# PAGE2-MAIN.net
KiCad netlist of a schematic drawn in Altium Designer
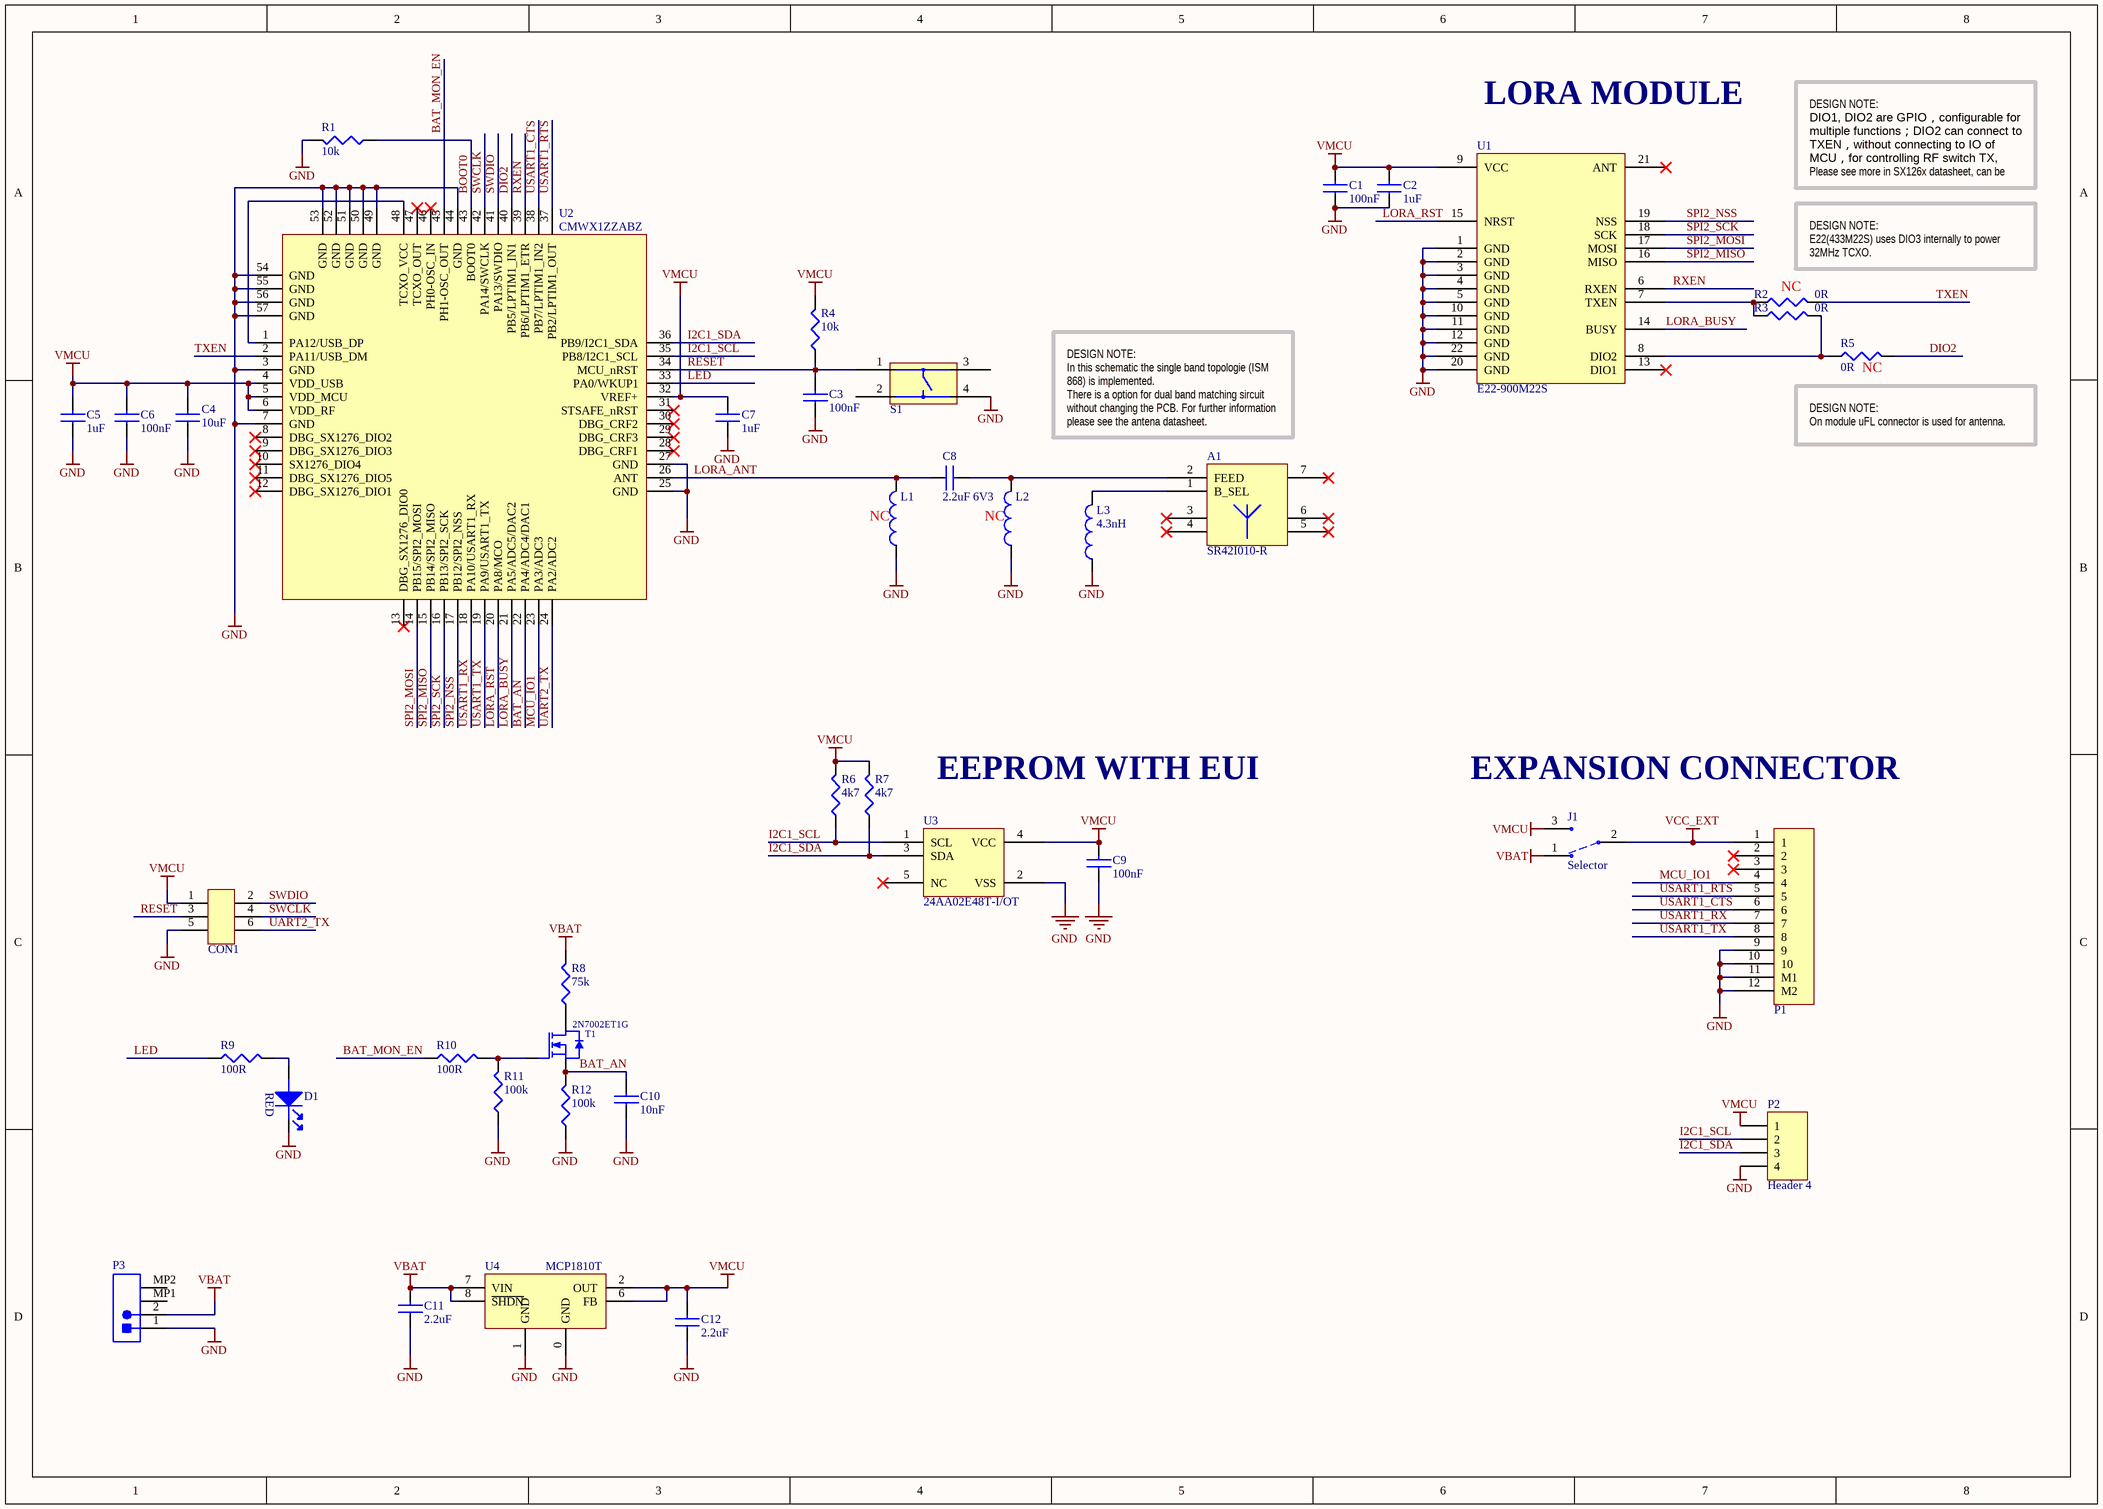
[diagram p0: PAGE2-MAIN.SchDoc]

(export (version "E")
  (design (tool "Eeschema 10.0.6"))
  (components
    (comp (ref "A1")
      (value "SR42I010-R")
      (footprint "LORA_PCB_ANTENNA")
      (description "Antenna SMD -4dBi Gain 870MHz/928MHz Automotive 7-Pin SMD T/R")
      (fields (field (name "MANUFACTURER") "Antenova"))
      (libsource (lib "Arribada-turtle-gps-tag-lora-addon") (part "SR42I010-R"))
    )
    (comp (ref "C1")
      (value "100nF")
      (footprint "CAP0603")
      (description "MURATA - GRM188R71C104KA01J - CAP, MLCC, X7R, 0.1UF, 16V, 0603")
      (fields
        (field (name "MANUFACTURER") "MURATA")
        (field (name "MANUFACTURER PART NUMBER") "GRM188R71C104KA01J")
      )
      (libsource (lib "Passive") (part "C - 100nF"))
    )
    (comp (ref "C2")
      (value "1uF")
      (footprint "CAP0603")
      (description "MURATA - GRM188R61H105KAALD - CAP, MLCC, X5R, 1UF, 50V, 0603")
      (fields
        (field (name "MANUFACTURER") "MURATA")
        (field (name "MANUFACTURER PART NUMBER") "GRM188R61H105KAALD")
      )
      (libsource (lib "Passive") (part "C - 1uF"))
    )
    (comp (ref "C3")
      (value "100nF")
      (footprint "CAP0603")
      (description "MURATA - GRM188R71C104KA01J - CAP, MLCC, X7R, 0.1UF, 16V, 0603")
      (fields
        (field (name "MANUFACTURER") "MURATA")
        (field (name "MANUFACTURER PART NUMBER") "GRM188R71C104KA01J")
      )
      (libsource (lib "Passive") (part "C - 100nF"))
    )
    (comp (ref "C4")
      (value "10uF")
      (footprint "CAP0603")
      (description "10uf/0603/20%")
      (fields
        (field (name "MANUFACTURER") "KEMET")
        (field (name "MANUFACTURER PART NUMBER") "C0603C106M8PACTU")
      )
      (libsource (lib "pira-smart-schlib") (part "10uF"))
    )
    (comp (ref "C5")
      (value "1uF")
      (footprint "CAP0603")
      (description "MURATA - GRM188R61H105KAALD - CAP, MLCC, X5R, 1UF, 50V, 0603")
      (fields
        (field (name "MANUFACTURER") "MURATA")
        (field (name "MANUFACTURER PART NUMBER") "GRM188R61H105KAALD")
      )
      (libsource (lib "Passive") (part "C - 1uF"))
    )
    (comp (ref "C6")
      (value "100nF")
      (footprint "CAP0603")
      (description "MURATA - GRM188R71C104KA01J - CAP, MLCC, X7R, 0.1UF, 16V, 0603")
      (fields
        (field (name "MANUFACTURER") "MURATA")
        (field (name "MANUFACTURER PART NUMBER") "GRM188R71C104KA01J")
      )
      (libsource (lib "Passive") (part "C - 100nF"))
    )
    (comp (ref "C7")
      (value "1uF")
      (footprint "CAP0603")
      (description "MURATA - GRM188R61H105KAALD - CAP, MLCC, X5R, 1UF, 50V, 0603")
      (fields
        (field (name "MANUFACTURER") "MURATA")
        (field (name "MANUFACTURER PART NUMBER") "GRM188R61H105KAALD")
      )
      (libsource (lib "Passive") (part "C - 1uF"))
    )
    (comp (ref "C8")
      (value "2.2uF 6V3")
      (footprint "CAP0402")
      (description "CAP CER 2.2UF 6.3V 20% X5R 0402")
      (fields
        (field (name "MANUFACTURER") "Murata")
        (field (name "MANUFACTURER PART NUMBER") "GRM155R60J225ME15D")
      )
      (libsource (lib "Passive") (part "C - 2.2uF/6V3/0402"))
    )
    (comp (ref "C9")
      (value "100nF")
      (footprint "CAP0603")
      (description "MURATA - GRM188R71C104KA01J - CAP, MLCC, X7R, 0.1UF, 16V, 0603")
      (fields
        (field (name "MANUFACTURER") "MURATA")
        (field (name "MANUFACTURER PART NUMBER") "GRM188R71C104KA01J")
      )
      (libsource (lib "Passive") (part "C - 100nF"))
    )
    (comp (ref "C10")
      (value "10nF")
      (footprint "CAP0603")
      (description "KEMET - C0603X103K5RECAUTO - CAP, MLCC, AEC-Q200, X7R, 0.01UF, 50V")
      (fields
        (field (name "MANUFACTURER") "TDK EPCOS")
        (field (name "MANUFACTURER PART NUMBER") "C0603X103K5RECAUTO")
      )
      (libsource (lib "Passive") (part "C - 10nF"))
    )
    (comp (ref "C11")
      (value "2.2uF")
      (footprint "CAP0805")
      (description "Multilayer Ceramic Capacitors MLCC - SMD/SMT 2.2uF 25V X7R 10%")
      (fields
        (field (name "MANUFACTURER") "Yageo")
        (field (name "MANUFACTURER PART NUMBER") "CC0805KKX7R8BB225")
      )
      (libsource (lib "Passive") (part "C - 2.2uF/0805"))
    )
    (comp (ref "C12")
      (value "2.2uF")
      (footprint "CAP0805")
      (description "Multilayer Ceramic Capacitors MLCC - SMD/SMT 2.2uF 25V X7R 10%")
      (fields
        (field (name "MANUFACTURER") "Yageo")
        (field (name "MANUFACTURER PART NUMBER") "CC0805KKX7R8BB225")
      )
      (libsource (lib "Passive") (part "C - 2.2uF/0805"))
    )
    (comp (ref "CON1")
      (value "Tag connect")
      (footprint "TC2030-IDC-NL")
      (libsource (lib "Connectors") (part "tag connecot 6 pin"))
    )
    (comp (ref "D1")
      (value "LED RED")
      (footprint "LED0603")
      (description "BROADCOM LIMITED - HSMS-C190 - LED, RED, 10MCD, 626NM")
      (fields
        (field (name "MANUFACTURER") "BROADCOM LIMITED")
        (field (name "MANUFACTURER PART NUMBER") "HSMS-C190")
      )
      (libsource (lib "Active") (part "LED - LED RED"))
    )
    (comp (ref "J1")
      (value "Selector")
      (footprint "Selector")
      (libsource (lib "Connectors") (part "Selector"))
    )
    (comp (ref "L1")
      (value "4.3nH")
      (footprint "IND0402")
      (description "Inductor RF Chip Multi-Layer 4.3nH 0.3nH 100MHz 8Q-Factor Air 300mA 210mOhm DCR 0402 Paper T/R")
      (fields
        (field (name "MANUFACTURER") "Murata")
        (field (name "MANUFACTURER PART NUMBER") "LQG15HN4N3S02D")
      )
      (libsource (lib "Passive") (part "L - 4.3nH/0402"))
    )
    (comp (ref "L2")
      (value "4.3nH")
      (footprint "IND0402")
      (description "Inductor RF Chip Multi-Layer 4.3nH 0.3nH 100MHz 8Q-Factor Air 300mA 210mOhm DCR 0402 Paper T/R")
      (fields
        (field (name "MANUFACTURER") "Murata")
        (field (name "MANUFACTURER PART NUMBER") "LQG15HN4N3S02D")
      )
      (libsource (lib "Passive") (part "L - 4.3nH/0402"))
    )
    (comp (ref "L3")
      (value "4.3nH")
      (footprint "IND0402")
      (description "Inductor RF Chip Multi-Layer 4.3nH 0.3nH 100MHz 8Q-Factor Air 300mA 210mOhm DCR 0402 Paper T/R")
      (fields
        (field (name "MANUFACTURER") "Murata")
        (field (name "MANUFACTURER PART NUMBER") "LQG15HN4N3S02D")
      )
      (libsource (lib "Inductors_Schlib") (part "4.3nH/0402"))
    )
    (comp (ref "P1")
      (value "53261-1071")
      (footprint "53261-1071")
      (description "Headers & Wire Housings 1.25MM HDR 10 CKT Right-Angle")
      (fields (field (name "MANUFACTURER") "Molex"))
      (libsource (lib "Schlib") (part "53261-1071"))
    )
    (comp (ref "P2")
      (value "Header 4")
      (footprint "HDR1X4")
      (description "Header, 4-Pin")
      (fields (field (name "PUBLISHER") "Altium Limited"))
      (libsource (lib "Miscellaneous Connectors") (part "Header 4"))
    )
    (comp (ref "P3")
      (value "S2B-PH-SM4-TB(LF)(SN)")
      (footprint "JST- S2B-PH-SM4-TB(LF)(SN)-2_V")
      (description "Male Header, Pitch 2 mm, 1 x 2 Position, Height 5.5 mm, -25 to 85 degC, RoHS, Tape and Reel")
      (libsource (lib "Schlib") (part "CMP-1755-00001-1"))
    )
    (comp (ref "R1")
      (value "10k")
      (footprint "RES0603")
      (description "MULTICOMP - MCMR06X103 JTL - RES, CERAMIC, 10K, 5%, 0.1W, 0603")
      (fields
        (field (name "MANUFACTURER") "MULTICOMP")
        (field (name "MANUFACTURER PART NUMBER") "MCMR06X103 JTL")
      )
      (libsource (lib "Passive") (part "R - 10k"))
    )
    (comp (ref "R2")
      (value "0R")
      (footprint "RES0603")
      (description "BOURNS - CR0603-J/-000ELF - RES, THICK FILM, 0R, 5%, 0.1W, 0603")
      (fields
        (field (name "MANUFACTURER") "BOURNS")
        (field (name "MANUFACTURER PART NUMBER") "CR0603-J/-000ELF")
      )
      (libsource (lib "Passive") (part "R - 0R"))
    )
    (comp (ref "R3")
      (value "0R")
      (footprint "RES0603")
      (description "BOURNS - CR0603-J/-000ELF - RES, THICK FILM, 0R, 5%, 0.1W, 0603")
      (fields
        (field (name "MANUFACTURER") "BOURNS")
        (field (name "MANUFACTURER PART NUMBER") "CR0603-J/-000ELF")
      )
      (libsource (lib "Passive") (part "R - 0R"))
    )
    (comp (ref "R4")
      (value "10k")
      (footprint "RES0603")
      (description "MULTICOMP - MCMR06X103 JTL - RES, CERAMIC, 10K, 5%, 0.1W, 0603")
      (fields
        (field (name "MANUFACTURER") "MULTICOMP")
        (field (name "MANUFACTURER PART NUMBER") "MCMR06X103 JTL")
      )
      (libsource (lib "Passive") (part "R - 10k"))
    )
    (comp (ref "R5")
      (value "0R")
      (footprint "RES0603")
      (description "BOURNS - CR0603-J/-000ELF - RES, THICK FILM, 0R, 5%, 0.1W, 0603")
      (fields
        (field (name "MANUFACTURER") "BOURNS")
        (field (name "MANUFACTURER PART NUMBER") "CR0603-J/-000ELF")
      )
      (libsource (lib "Passive") (part "R - 0R"))
    )
    (comp (ref "R6")
      (value "4k7")
      (footprint "RES0603")
      (description "MULTICOMP - MCMR06X4701FTL - RES, CERAMIC, 4K7, 1%, 0.1W, 0603")
      (fields
        (field (name "MANUFACTURER") "MULTICOMP")
        (field (name "MANUFACTURER PART NUMBER") "MCMR06X4701FTL")
      )
      (libsource (lib "Passive") (part "R - 4k7"))
    )
    (comp (ref "R7")
      (value "4k7")
      (footprint "RES0603")
      (description "MULTICOMP - MCMR06X4701FTL - RES, CERAMIC, 4K7, 1%, 0.1W, 0603")
      (fields
        (field (name "MANUFACTURER") "MULTICOMP")
        (field (name "MANUFACTURER PART NUMBER") "MCMR06X4701FTL")
      )
      (libsource (lib "Passive") (part "R - 4k7"))
    )
    (comp (ref "R8")
      (value "75k")
      (footprint "RES0603")
      (description "MULTICOMP - MCSR06X7502FTL - RES, CERAMIC, 75K, 1%, 0.1W, 0603")
      (fields
        (field (name "MANUFACTURER") "MULTICOMP")
        (field (name "MANUFACTURER PART NUMBER") "MCSR06X7502FTL")
      )
      (libsource (lib "Passive") (part "R - 75k"))
    )
    (comp (ref "R9")
      (value "100R")
      (footprint "RES0603")
      (description "MULTICOMP - MC0063W06031100R - RES, THICK FILM, 100R, 1%, 0.063W, 0603")
      (fields
        (field (name "MANUFACTURER") "MULTICOMP")
        (field (name "MANUFACTURER PART NUMBER") "MC0063W06031100R")
      )
      (libsource (lib "Passive") (part "R - 100R"))
    )
    (comp (ref "R10")
      (value "100R")
      (footprint "RES0603")
      (description "MULTICOMP - MC0063W06031100R - RES, THICK FILM, 100R, 1%, 0.063W, 0603")
      (fields
        (field (name "MANUFACTURER") "MULTICOMP")
        (field (name "MANUFACTURER PART NUMBER") "MC0063W06031100R")
      )
      (libsource (lib "Passive") (part "R - 100R"))
    )
    (comp (ref "R11")
      (value "100k")
      (footprint "RES0603")
      (description "MULTICOMP - MCMR06X104 JTL - RES, CERAMIC, 100K, 5%, 0.1W, 0603")
      (fields
        (field (name "MANUFACTURER") "MULTICOMP")
        (field (name "MANUFACTURER PART NUMBER") "MCMR06X104 JTL")
      )
      (libsource (lib "Passive") (part "R - 100k"))
    )
    (comp (ref "R12")
      (value "100k")
      (footprint "RES0603")
      (description "MULTICOMP - MCMR06X104 JTL - RES, CERAMIC, 100K, 5%, 0.1W, 0603")
      (fields
        (field (name "MANUFACTURER") "MULTICOMP")
        (field (name "MANUFACTURER PART NUMBER") "MCMR06X104 JTL")
      )
      (libsource (lib "Passive") (part "R - 100k"))
    )
    (comp (ref "S1")
      (value "KMR221NGLFS")
      (footprint "SW")
      (description "SWITCH TACTILE SPST-NO 0.05A 32V")
      (fields (field (name "MANUFACTURER") "ITT C&K"))
      (libsource (lib "Schlib") (part "KMR221NGLFS"))
    )
    (comp (ref "T1")
      (value "2N7002ET1G")
      (footprint "Active:SOT23-3AL")
      (description "MOSFET Transistor, N Channel, 310 mA, 60 V, 0.86 ohm, 10 V, 1 V")
      (fields (field (name "AUTHOR") "Ciril Golob"))
      (libsource (lib "Active") (part "T_M - 2N7002ET1G"))
    )
    (comp (ref "U1")
      (value "E22-900M22S")
      (footprint "E22-900M22S")
      (libsource (lib "Lora_modules") (part "E22-900M22S"))
    )
    (comp (ref "U2")
      (value "CMWX1ZZABZ")
      (footprint "Lora Module ES0")
      (description "RF Module, FSK, OOK, LoRa, 4.8Kbps, 915MHz, -135.5dBm, 2.2V to 3.6V, I2C, SPI, UART, USB")
      (fields
        (field (name "MANUFACTURER") "Murata")
        (field (name "MANUFACTURER PART NUMBER") "CMWX1ZZABZ-091")
      )
      (libsource (lib "Active") (part "MCU - CMWX1ZZABZ"))
    )
    (comp (ref "U3")
      (value "24AA02E48T-I/OT")
      (footprint "SOT95P280X145-5N")
      (fields (field (name "MANUFACTURER") "Microchip"))
      (libsource (lib "Arribada-turtle-gps-tag-lora-addon") (part "24AA02E48T-I/OT"))
    )
    (comp (ref "U4")
      (value "MCP1810T")
      (footprint "VDFN_2x2")
      (description "LDO Voltage Regulator, Fixed, 2.5 V to 5.5 V in, 2.5 V/150 mA out, 380 mV drop")
      (fields
        (field (name "MANUFACTURER") "ON SEMICONDUCTOR")
        (field (name "MANUFACTURER PART NUMBER") "LM2596DSADJG")
      )
      (libsource (lib "Active") (part "V_LIN - MCP1810T"))
    )
  )
  (nets
    (net (code "1") (name "/BAT_AN") (class "Default")
      (node (ref "C10") (pin "2") (pinfunction "2_2") (pintype "passive"))
      (node (ref "R12") (pin "2") (pinfunction "2_2") (pintype "passive"))
      (node (ref "T1") (pin "2") (pinfunction "S_2") (pintype "passive"))
      (node (ref "U2") (pin "22") (pinfunction "PA4/ADC4/DAC1_22") (pintype "passive"))
    )
    (net (code "2") (name "/BAT_MON_EN") (class "Default")
      (node (ref "R10") (pin "1") (pinfunction "1_1") (pintype "passive"))
      (node (ref "U2") (pin "45") (pinfunction "PH1-OSC_OUT_45") (pintype "passive"))
    )
    (net (code "3") (name "/BOOT0") (class "Default")
      (node (ref "R1") (pin "1") (pinfunction "1_1") (pintype "passive"))
      (node (ref "U2") (pin "43") (pinfunction "BOOT0_43") (pintype "passive"))
    )
    (net (code "4") (name "/DIO2") (class "Default")
      (node (ref "R5") (pin "2") (pinfunction "2_2") (pintype "passive"))
      (node (ref "U2") (pin "40") (pinfunction "PB5/LPTIM1_IN1_40") (pintype "passive"))
    )
    (net (code "5") (name "/I2C1_SCL") (class "Default")
      (node (ref "P2") (pin "2") (pinfunction "2_2") (pintype "passive"))
      (node (ref "R6") (pin "1") (pinfunction "1_1") (pintype "passive"))
      (node (ref "U2") (pin "35") (pinfunction "PB8/I2C1_SCL_35") (pintype "passive"))
      (node (ref "U3") (pin "1") (pinfunction "SCL_1") (pintype "passive"))
    )
    (net (code "6") (name "/I2C1_SDA") (class "Default")
      (node (ref "P2") (pin "3") (pinfunction "3_3") (pintype "passive"))
      (node (ref "R7") (pin "1") (pinfunction "1_1") (pintype "passive"))
      (node (ref "U2") (pin "36") (pinfunction "PB9/I2C1_SDA_36") (pintype "passive"))
      (node (ref "U3") (pin "3") (pinfunction "SDA_3") (pintype "passive"))
    )
    (net (code "7") (name "/LED") (class "Default")
      (node (ref "R9") (pin "1") (pinfunction "1_1") (pintype "passive"))
      (node (ref "U2") (pin "33") (pinfunction "PA0/WKUP1_33") (pintype "passive"))
    )
    (net (code "8") (name "/LORA_ANT") (class "Default")
      (node (ref "C8") (pin "1") (pinfunction "1_1") (pintype "passive"))
      (node (ref "L1") (pin "2") (pinfunction "2_2") (pintype "passive"))
      (node (ref "U2") (pin "26") (pinfunction "ANT_26") (pintype "passive"))
    )
    (net (code "9") (name "/LORA_BUSY") (class "Default")
      (node (ref "U1") (pin "14") (pinfunction "BUSY_14") (pintype "passive"))
      (node (ref "U2") (pin "21") (pinfunction "PA5/ADC5/DAC2_21") (pintype "passive"))
    )
    (net (code "10") (name "/LORA_RST") (class "Default")
      (node (ref "U1") (pin "15") (pinfunction "NRST_15") (pintype "passive"))
      (node (ref "U2") (pin "20") (pinfunction "PA8/MCO_20") (pintype "passive"))
    )
    (net (code "11") (name "/MCU_IO1") (class "Default")
      (node (ref "P1") (pin "4") (pinfunction "4_4") (pintype "passive"))
      (node (ref "U2") (pin "23") (pinfunction "PA3/ADC3_23") (pintype "passive"))
    )
    (net (code "12") (name "/RESET") (class "Default")
      (node (ref "C3") (pin "2") (pinfunction "2_2") (pintype "passive"))
      (node (ref "CON1") (pin "3") (pinfunction "3_3") (pintype "open_collector"))
      (node (ref "R4") (pin "1") (pinfunction "1_1") (pintype "passive"))
      (node (ref "S1") (pin "1") (pinfunction "1_1") (pintype "passive"))
      (node (ref "U2") (pin "34") (pinfunction "MCU_nRST_34") (pintype "passive"))
    )
    (net (code "13") (name "/RXEN") (class "Default")
      (node (ref "U1") (pin "6") (pinfunction "RXEN_6") (pintype "passive"))
      (node (ref "U2") (pin "39") (pinfunction "PB6/LPTIM1_ETR_39") (pintype "passive"))
    )
    (net (code "14") (name "/SPI2_MISO") (class "Default")
      (node (ref "U1") (pin "16") (pinfunction "MISO_16") (pintype "passive"))
      (node (ref "U2") (pin "15") (pinfunction "PB14/SPI2_MISO_15") (pintype "passive"))
    )
    (net (code "15") (name "/SPI2_MOSI") (class "Default")
      (node (ref "U1") (pin "17") (pinfunction "MOSI_17") (pintype "passive"))
      (node (ref "U2") (pin "14") (pinfunction "PB15/SPI2_MOSI_14") (pintype "passive"))
    )
    (net (code "16") (name "/SPI2_NSS") (class "Default")
      (node (ref "U1") (pin "19") (pinfunction "NSS_19") (pintype "passive"))
      (node (ref "U2") (pin "17") (pinfunction "PB12/SPI2_NSS_17") (pintype "passive"))
    )
    (net (code "17") (name "/SPI2_SCK") (class "Default")
      (node (ref "U1") (pin "18") (pinfunction "SCK_18") (pintype "passive"))
      (node (ref "U2") (pin "16") (pinfunction "PB13/SPI2_SCK_16") (pintype "passive"))
    )
    (net (code "18") (name "/SWCLK") (class "Default")
      (node (ref "CON1") (pin "4") (pinfunction "4_4") (pintype "open_collector"))
      (node (ref "U2") (pin "42") (pinfunction "PA14/SWCLK_42") (pintype "passive"))
    )
    (net (code "19") (name "/SWDIO") (class "Default")
      (node (ref "CON1") (pin "2") (pinfunction "2_2") (pintype "open_collector"))
      (node (ref "U2") (pin "41") (pinfunction "PA13/SWDIO_41") (pintype "passive"))
    )
    (net (code "20") (name "/TXEN") (class "Default")
      (node (ref "R2") (pin "2") (pinfunction "2_2") (pintype "passive"))
      (node (ref "U2") (pin "2") (pinfunction "PA11/USB_DM_2") (pintype "passive"))
    )
    (net (code "21") (name "/UART2_TX") (class "Default")
      (node (ref "CON1") (pin "6") (pinfunction "6_6") (pintype "passive"))
      (node (ref "U2") (pin "24") (pinfunction "PA2/ADC2_24") (pintype "passive"))
    )
    (net (code "22") (name "/USART1_CTS") (class "Default")
      (node (ref "P1") (pin "6") (pinfunction "6_6") (pintype "passive"))
      (node (ref "U2") (pin "38") (pinfunction "PB7/LPTIM1_IN2_38") (pintype "passive"))
    )
    (net (code "23") (name "/USART1_RTS") (class "Default")
      (node (ref "P1") (pin "5") (pinfunction "5_5") (pintype "passive"))
      (node (ref "U2") (pin "37") (pinfunction "PB2/LPTIM1_OUT_37") (pintype "passive"))
    )
    (net (code "24") (name "/USART1_RX") (class "Default")
      (node (ref "P1") (pin "7") (pinfunction "7_7") (pintype "passive"))
      (node (ref "U2") (pin "18") (pinfunction "PA10/USART1_RX_18") (pintype "passive"))
    )
    (net (code "25") (name "/USART1_TX") (class "Default")
      (node (ref "P1") (pin "8") (pinfunction "8_8") (pintype "passive"))
      (node (ref "U2") (pin "19") (pinfunction "PA9/USART1_TX_19") (pintype "passive"))
    )
    (net (code "26") (name "GND") (class "Default")
      (node (ref "C1") (pin "1") (pinfunction "1_1") (pintype "passive"))
      (node (ref "C10") (pin "1") (pinfunction "1_1") (pintype "passive"))
      (node (ref "C11") (pin "1") (pinfunction "1_1") (pintype "passive"))
      (node (ref "C12") (pin "1") (pinfunction "1_1") (pintype "passive"))
      (node (ref "C2") (pin "1") (pinfunction "1_1") (pintype "passive"))
      (node (ref "C3") (pin "1") (pinfunction "1_1") (pintype "passive"))
      (node (ref "C4") (pin "1") (pinfunction "1_1") (pintype "passive"))
      (node (ref "C5") (pin "1") (pinfunction "1_1") (pintype "passive"))
      (node (ref "C6") (pin "1") (pinfunction "1_1") (pintype "passive"))
      (node (ref "C7") (pin "1") (pinfunction "1_1") (pintype "passive"))
      (node (ref "C9") (pin "1") (pinfunction "1_1") (pintype "passive"))
      (node (ref "CON1") (pin "5") (pinfunction "5_5") (pintype "open_collector"))
      (node (ref "D1") (pin "1") (pinfunction "cathode_1") (pintype "passive"))
      (node (ref "L1") (pin "1") (pinfunction "1_1") (pintype "passive"))
      (node (ref "L2") (pin "1") (pinfunction "1_1") (pintype "passive"))
      (node (ref "L3") (pin "1") (pinfunction "1_1") (pintype "passive"))
      (node (ref "P1") (pin "10") (pinfunction "10_10") (pintype "passive"))
      (node (ref "P1") (pin "11") (pinfunction "M1_11") (pintype "passive"))
      (node (ref "P1") (pin "12") (pinfunction "M2_12") (pintype "passive"))
      (node (ref "P1") (pin "9") (pinfunction "9_9") (pintype "passive"))
      (node (ref "P2") (pin "4") (pinfunction "4_4") (pintype "passive"))
      (node (ref "P3") (pin "1") (pinfunction "1_1") (pintype "passive"))
      (node (ref "R1") (pin "2") (pinfunction "2_2") (pintype "passive"))
      (node (ref "R11") (pin "1") (pinfunction "1_1") (pintype "passive"))
      (node (ref "R12") (pin "1") (pinfunction "1_1") (pintype "passive"))
      (node (ref "S1") (pin "4") (pinfunction "4_4") (pintype "passive"))
      (node (ref "U1") (pin "1") (pinfunction "GND_1") (pintype "passive"))
      (node (ref "U1") (pin "10") (pinfunction "GND_10") (pintype "passive"))
      (node (ref "U1") (pin "11") (pinfunction "GND_11") (pintype "passive"))
      (node (ref "U1") (pin "12") (pinfunction "GND_12") (pintype "passive"))
      (node (ref "U1") (pin "2") (pinfunction "GND_2") (pintype "passive"))
      (node (ref "U1") (pin "20") (pinfunction "GND_20") (pintype "passive"))
      (node (ref "U1") (pin "22") (pinfunction "GND_22") (pintype "passive"))
      (node (ref "U1") (pin "3") (pinfunction "GND_3") (pintype "passive"))
      (node (ref "U1") (pin "4") (pinfunction "GND_4") (pintype "passive"))
      (node (ref "U1") (pin "5") (pinfunction "GND_5") (pintype "passive"))
      (node (ref "U2") (pin "25") (pinfunction "GND_25") (pintype "passive"))
      (node (ref "U2") (pin "27") (pinfunction "GND_27") (pintype "passive"))
      (node (ref "U2") (pin "3") (pinfunction "GND_3") (pintype "passive"))
      (node (ref "U2") (pin "44") (pinfunction "GND_44") (pintype "passive"))
      (node (ref "U2") (pin "49") (pinfunction "GND_49") (pintype "passive"))
      (node (ref "U2") (pin "50") (pinfunction "GND_50") (pintype "passive"))
      (node (ref "U2") (pin "51") (pinfunction "GND_51") (pintype "passive"))
      (node (ref "U2") (pin "52") (pinfunction "GND_52") (pintype "passive"))
      (node (ref "U2") (pin "53") (pinfunction "GND_53") (pintype "passive"))
      (node (ref "U2") (pin "54") (pinfunction "GND_54") (pintype "passive"))
      (node (ref "U2") (pin "55") (pinfunction "GND_55") (pintype "passive"))
      (node (ref "U2") (pin "56") (pinfunction "GND_56") (pintype "passive"))
      (node (ref "U2") (pin "57") (pinfunction "GND_57") (pintype "passive"))
      (node (ref "U2") (pin "7") (pinfunction "GND_7") (pintype "passive"))
      (node (ref "U3") (pin "2") (pinfunction "VSS_2") (pintype "passive"))
      (node (ref "U4") (pin "0") (pinfunction "GND_0") (pintype "open_collector"))
      (node (ref "U4") (pin "1") (pinfunction "GND_1") (pintype "open_collector"))
    )
    (net (code "27") (name "Net-(A1-B_SEL)") (class "Default")
      (node (ref "A1") (pin "1") (pinfunction "B_SEL_1") (pintype "passive"))
      (node (ref "L3") (pin "2") (pinfunction "2_2") (pintype "passive"))
    )
    (net (code "28") (name "Net-(A1-FEED)") (class "Default")
      (node (ref "A1") (pin "2") (pinfunction "FEED_2") (pintype "passive"))
      (node (ref "C8") (pin "2") (pinfunction "2_2") (pintype "passive"))
      (node (ref "L2") (pin "2") (pinfunction "2_2") (pintype "passive"))
    )
    (net (code "29") (name "Net-(D1-ANODE)") (class "Default")
      (node (ref "D1") (pin "2") (pinfunction "ANODE_2") (pintype "passive"))
      (node (ref "R9") (pin "2") (pinfunction "2_2") (pintype "passive"))
    )
    (net (code "30") (name "Net-(T1-D)") (class "Default")
      (node (ref "R8") (pin "1") (pinfunction "1_1") (pintype "passive"))
      (node (ref "T1") (pin "3") (pinfunction "D_3") (pintype "passive"))
    )
    (net (code "31") (name "Net-(T1-G)") (class "Default")
      (node (ref "R10") (pin "2") (pinfunction "2_2") (pintype "passive"))
      (node (ref "R11") (pin "2") (pinfunction "2_2") (pintype "passive"))
      (node (ref "T1") (pin "1") (pinfunction "G_1") (pintype "passive"))
    )
    (net (code "32") (name "Net-(U1-DIO2)") (class "Default")
      (node (ref "R3") (pin "2") (pinfunction "2_2") (pintype "passive"))
      (node (ref "R5") (pin "1") (pinfunction "1_1") (pintype "passive"))
      (node (ref "U1") (pin "8") (pinfunction "DIO2_8") (pintype "passive"))
    )
    (net (code "33") (name "Net-(U1-TXEN)") (class "Default")
      (node (ref "R2") (pin "1") (pinfunction "1_1") (pintype "passive"))
      (node (ref "R3") (pin "1") (pinfunction "1_1") (pintype "passive"))
      (node (ref "U1") (pin "7") (pinfunction "TXEN_7") (pintype "passive"))
    )
    (net (code "34") (name "Net-(U2-PA12{slash}USB_DP)") (class "Default")
      (node (ref "U2") (pin "1") (pinfunction "PA12/USB_DP_1") (pintype "passive"))
      (node (ref "U2") (pin "48") (pinfunction "TCXO_VCC_48") (pintype "passive"))
    )
    (net (code "35") (name "VBAT") (class "Default")
      (node (ref "C11") (pin "2") (pinfunction "2_2") (pintype "passive"))
      (node (ref "J1") (pin "1") (pinfunction "1_1") (pintype "passive"))
      (node (ref "P3") (pin "2") (pinfunction "2_2") (pintype "passive"))
      (node (ref "R8") (pin "2") (pinfunction "2_2") (pintype "passive"))
      (node (ref "U4") (pin "7") (pinfunction "VIN_7") (pintype "open_collector"))
      (node (ref "U4") (pin "8") (pinfunction "~{SHDN}_8") (pintype "open_collector"))
    )
    (net (code "36") (name "VCC_EXT") (class "Default")
      (node (ref "J1") (pin "2") (pinfunction "2_2") (pintype "passive"))
      (node (ref "P1") (pin "1") (pinfunction "1_1") (pintype "passive"))
    )
    (net (code "37") (name "VMCU") (class "Default")
      (node (ref "C1") (pin "2") (pinfunction "2_2") (pintype "passive"))
      (node (ref "C12") (pin "2") (pinfunction "2_2") (pintype "passive"))
      (node (ref "C2") (pin "2") (pinfunction "2_2") (pintype "passive"))
      (node (ref "C4") (pin "2") (pinfunction "2_2") (pintype "passive"))
      (node (ref "C5") (pin "2") (pinfunction "2_2") (pintype "passive"))
      (node (ref "C6") (pin "2") (pinfunction "2_2") (pintype "passive"))
      (node (ref "C7") (pin "2") (pinfunction "2_2") (pintype "passive"))
      (node (ref "C9") (pin "2") (pinfunction "2_2") (pintype "passive"))
      (node (ref "CON1") (pin "1") (pinfunction "1_1") (pintype "open_collector"))
      (node (ref "J1") (pin "3") (pinfunction "3_3") (pintype "passive"))
      (node (ref "P2") (pin "1") (pinfunction "1_1") (pintype "passive"))
      (node (ref "R4") (pin "2") (pinfunction "2_2") (pintype "passive"))
      (node (ref "R6") (pin "2") (pinfunction "2_2") (pintype "passive"))
      (node (ref "R7") (pin "2") (pinfunction "2_2") (pintype "passive"))
      (node (ref "U1") (pin "9") (pinfunction "VCC_9") (pintype "passive"))
      (node (ref "U2") (pin "32") (pinfunction "VREF+_32") (pintype "passive"))
      (node (ref "U2") (pin "4") (pinfunction "VDD_USB_4") (pintype "passive"))
      (node (ref "U2") (pin "5") (pinfunction "VDD_MCU_5") (pintype "passive"))
      (node (ref "U2") (pin "6") (pinfunction "VDD_RF_6") (pintype "passive"))
      (node (ref "U3") (pin "4") (pinfunction "VCC_4") (pintype "passive"))
      (node (ref "U4") (pin "2") (pinfunction "OUT_2") (pintype "open_collector"))
      (node (ref "U4") (pin "6") (pinfunction "FB_6") (pintype "open_collector"))
    )
    (net (code "38") (name "unconnected-(A1-Pad3)") (class "Default")
      (node (ref "A1") (pin "3") (pintype "passive+no_connect"))
    )
    (net (code "39") (name "unconnected-(A1-Pad4)") (class "Default")
      (node (ref "A1") (pin "4") (pintype "passive+no_connect"))
    )
    (net (code "40") (name "unconnected-(A1-Pad5)") (class "Default")
      (node (ref "A1") (pin "5") (pintype "passive+no_connect"))
    )
    (net (code "41") (name "unconnected-(A1-Pad6)") (class "Default")
      (node (ref "A1") (pin "6") (pintype "passive+no_connect"))
    )
    (net (code "42") (name "unconnected-(A1-Pad7)") (class "Default")
      (node (ref "A1") (pin "7") (pintype "passive+no_connect"))
    )
    (net (code "43") (name "unconnected-(P1-Pad2)") (class "Default")
      (node (ref "P1") (pin "2") (pinfunction "2_2") (pintype "passive+no_connect"))
    )
    (net (code "44") (name "unconnected-(P1-Pad3)") (class "Default")
      (node (ref "P1") (pin "3") (pinfunction "3_3") (pintype "passive+no_connect"))
    )
    (net (code "45") (name "unconnected-(P3-PadMP1)") (class "Default")
      (node (ref "P3") (pin "MP1") (pinfunction "MP1_MP1") (pintype "passive"))
    )
    (net (code "46") (name "unconnected-(P3-PadMP2)") (class "Default")
      (node (ref "P3") (pin "MP2") (pinfunction "MP2_MP2") (pintype "passive"))
    )
    (net (code "47") (name "unconnected-(S1-Pad2)") (class "Default")
      (node (ref "S1") (pin "2") (pinfunction "2_2") (pintype "passive"))
    )
    (net (code "48") (name "unconnected-(S1-Pad3)") (class "Default")
      (node (ref "S1") (pin "3") (pinfunction "3_3") (pintype "passive"))
    )
    (net (code "49") (name "unconnected-(U1-ANT-Pad21)") (class "Default")
      (node (ref "U1") (pin "21") (pinfunction "ANT_21") (pintype "passive+no_connect"))
    )
    (net (code "50") (name "unconnected-(U1-DIO1-Pad13)") (class "Default")
      (node (ref "U1") (pin "13") (pinfunction "DIO1_13") (pintype "passive+no_connect"))
    )
    (net (code "51") (name "unconnected-(U2-DBG_CRF1-Pad28)") (class "Default")
      (node (ref "U2") (pin "28") (pinfunction "DBG_CRF1_28") (pintype "passive+no_connect"))
    )
    (net (code "52") (name "unconnected-(U2-DBG_CRF2-Pad30)") (class "Default")
      (node (ref "U2") (pin "30") (pinfunction "DBG_CRF2_30") (pintype "passive+no_connect"))
    )
    (net (code "53") (name "unconnected-(U2-DBG_CRF3-Pad29)") (class "Default")
      (node (ref "U2") (pin "29") (pinfunction "DBG_CRF3_29") (pintype "passive+no_connect"))
    )
    (net (code "54") (name "unconnected-(U2-DBG_SX1276_DIO0-Pad13)") (class "Default")
      (node (ref "U2") (pin "13") (pinfunction "DBG_SX1276_DIO0_13") (pintype "passive+no_connect"))
    )
    (net (code "55") (name "unconnected-(U2-DBG_SX1276_DIO1-Pad12)") (class "Default")
      (node (ref "U2") (pin "12") (pinfunction "DBG_SX1276_DIO1_12") (pintype "passive+no_connect"))
    )
    (net (code "56") (name "unconnected-(U2-DBG_SX1276_DIO2-Pad8)") (class "Default")
      (node (ref "U2") (pin "8") (pinfunction "DBG_SX1276_DIO2_8") (pintype "passive+no_connect"))
    )
    (net (code "57") (name "unconnected-(U2-DBG_SX1276_DIO3-Pad9)") (class "Default")
      (node (ref "U2") (pin "9") (pinfunction "DBG_SX1276_DIO3_9") (pintype "passive+no_connect"))
    )
    (net (code "58") (name "unconnected-(U2-DBG_SX1276_DIO5-Pad11)") (class "Default")
      (node (ref "U2") (pin "11") (pinfunction "DBG_SX1276_DIO5_11") (pintype "passive+no_connect"))
    )
    (net (code "59") (name "unconnected-(U2-PH0-OSC_IN-Pad46)") (class "Default")
      (node (ref "U2") (pin "46") (pinfunction "PH0-OSC_IN_46") (pintype "passive+no_connect"))
    )
    (net (code "60") (name "unconnected-(U2-STSAFE_nRST-Pad31)") (class "Default")
      (node (ref "U2") (pin "31") (pinfunction "STSAFE_nRST_31") (pintype "passive+no_connect"))
    )
    (net (code "61") (name "unconnected-(U2-SX1276_DIO4-Pad10)") (class "Default")
      (node (ref "U2") (pin "10") (pinfunction "SX1276_DIO4_10") (pintype "passive+no_connect"))
    )
    (net (code "62") (name "unconnected-(U2-TCXO_OUT-Pad47)") (class "Default")
      (node (ref "U2") (pin "47") (pinfunction "TCXO_OUT_47") (pintype "passive+no_connect"))
    )
    (net (code "63") (name "unconnected-(U3-NC-Pad5)") (class "Default")
      (node (ref "U3") (pin "5") (pinfunction "NC_5") (pintype "passive+no_connect"))
    )
  )
)
